# BlackChat_China_Tx.net
KiCad netlist of a schematic drawn in Altium Designer
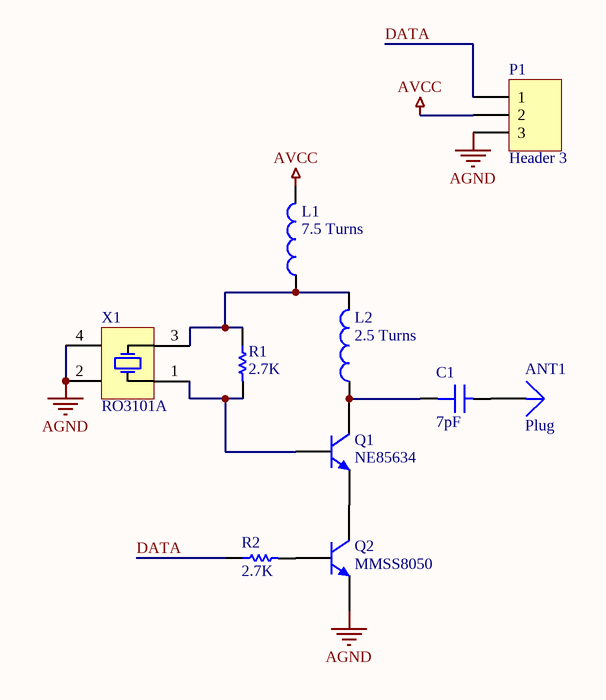
[diagram p0: BlackChat China Tx.SchDoc]

(export (version "E")
  (design (tool "Eeschema 10.0.6"))
  (components
    (comp (ref "ANT1")
      (value "Plug")
      (footprint "PIN1")
      (fields (field (name "PUBLISHER") "Altium Limited"))
      (libsource (lib "Miscellaneous Connectors") (part "Plug"))
    )
    (comp (ref "C1")
      (value "7pF")
      (footprint "CAP-0805")
      (description "SMD Chip Capacitor")
      (libsource (lib "BlackChat Library") (part "CHIP-CAP"))
    )
    (comp (ref "L1")
      (value "7.5 Turns")
      (footprint "AXIAL-0.4")
      (description "Generic Inductor")
      (libsource (lib "BlackChat Library") (part "Inductor"))
    )
    (comp (ref "L2")
      (value "2.5 Turns")
      (footprint "AXIAL-0.3")
      (description "Generic Inductor")
      (libsource (lib "BlackChat Library") (part "Inductor"))
    )
    (comp (ref "P1")
      (value "Header 3")
      (footprint "HDR1X3")
      (description "Header, 3-Pin")
      (fields (field (name "PUBLISHER") "Altium Limited"))
      (libsource (lib "Miscellaneous Connectors") (part "Header 3"))
    )
    (comp (ref "Q1")
      (value "NE85634")
      (footprint "NE85634_SOT89")
      (description "NPN RF SILICON TRANSISTOR")
      (libsource (lib "BlackChat Library") (part "NE85634"))
    )
    (comp (ref "Q2")
      (value "MMSS8050")
      (footprint "SOT95P275X120-3N")
      (description "NPN SILICON TRANSISTOR")
      (libsource (lib "BlackChat Library") (part "MMSS8050"))
    )
    (comp (ref "R1")
      (value "2.7K")
      (footprint "RES-0805")
      (description "SMD Chip Resistor")
      (libsource (lib "BlackChat Library") (part "CHIP-RES"))
    )
    (comp (ref "R2")
      (value "2.7K")
      (footprint "RES-0805")
      (description "SMD Chip Resistor")
      (libsource (lib "BlackChat Library") (part "CHIP-RES"))
    )
    (comp (ref "X1")
      (value "RO3101A")
      (footprint "RO3101A")
      (description "433.92 MHz  SAW  Resonator")
      (libsource (lib "BlackChat Library") (part "RO3101A"))
    )
  )
  (nets
    (net (code "1") (name "/DATA") (class "Default")
      (node (ref "P1") (pin "1") (pinfunction "1_1") (pintype "passive"))
      (node (ref "R2") (pin "1") (pinfunction "1_1") (pintype "passive"))
    )
    (net (code "2") (name "AGND") (class "Default")
      (node (ref "P1") (pin "3") (pinfunction "3_3") (pintype "passive"))
      (node (ref "Q2") (pin "1") (pinfunction "E_1") (pintype "passive"))
      (node (ref "X1") (pin "2") (pinfunction "CASE_2") (pintype "passive"))
      (node (ref "X1") (pin "4") (pinfunction "CASE_4") (pintype "passive"))
    )
    (net (code "3") (name "AVCC") (class "Default")
      (node (ref "L1") (pin "2") (pinfunction "2_2") (pintype "passive"))
      (node (ref "P1") (pin "2") (pinfunction "2_2") (pintype "passive"))
    )
    (net (code "4") (name "Net-(ANT1-Pad1)") (class "Default")
      (node (ref "ANT1") (pin "1") (pinfunction "1_1") (pintype "passive"))
      (node (ref "C1") (pin "2") (pinfunction "2_2") (pintype "passive"))
    )
    (net (code "5") (name "Net-(Q1-B)") (class "Default")
      (node (ref "Q1") (pin "1") (pinfunction "B_1") (pintype "passive"))
      (node (ref "R1") (pin "2") (pinfunction "2_2") (pintype "passive"))
      (node (ref "X1") (pin "1") (pinfunction "Terminal_1_1") (pintype "passive"))
    )
    (net (code "6") (name "Net-(Q1-C)") (class "Default")
      (node (ref "C1") (pin "1") (pinfunction "1_1") (pintype "passive"))
      (node (ref "L2") (pin "1") (pinfunction "1_1") (pintype "passive"))
      (node (ref "Q1") (pin "2") (pinfunction "C_2") (pintype "passive"))
    )
    (net (code "7") (name "Net-(Q1-E)") (class "Default")
      (node (ref "Q1") (pin "3") (pinfunction "E_3") (pintype "passive"))
      (node (ref "Q2") (pin "3") (pinfunction "C_3") (pintype "passive"))
    )
    (net (code "8") (name "Net-(Q2-B)") (class "Default")
      (node (ref "Q2") (pin "2") (pinfunction "B_2") (pintype "passive"))
      (node (ref "R2") (pin "2") (pinfunction "2_2") (pintype "passive"))
    )
    (net (code "9") (name "Net-(X1-Terminal_2)") (class "Default")
      (node (ref "L1") (pin "1") (pinfunction "1_1") (pintype "passive"))
      (node (ref "L2") (pin "2") (pinfunction "2_2") (pintype "passive"))
      (node (ref "R1") (pin "1") (pinfunction "1_1") (pintype "passive"))
      (node (ref "X1") (pin "3") (pinfunction "Terminal_2_3") (pintype "passive"))
    )
  )
)
